# theFlower.net
KiCad netlist of a schematic drawn in EAGLE
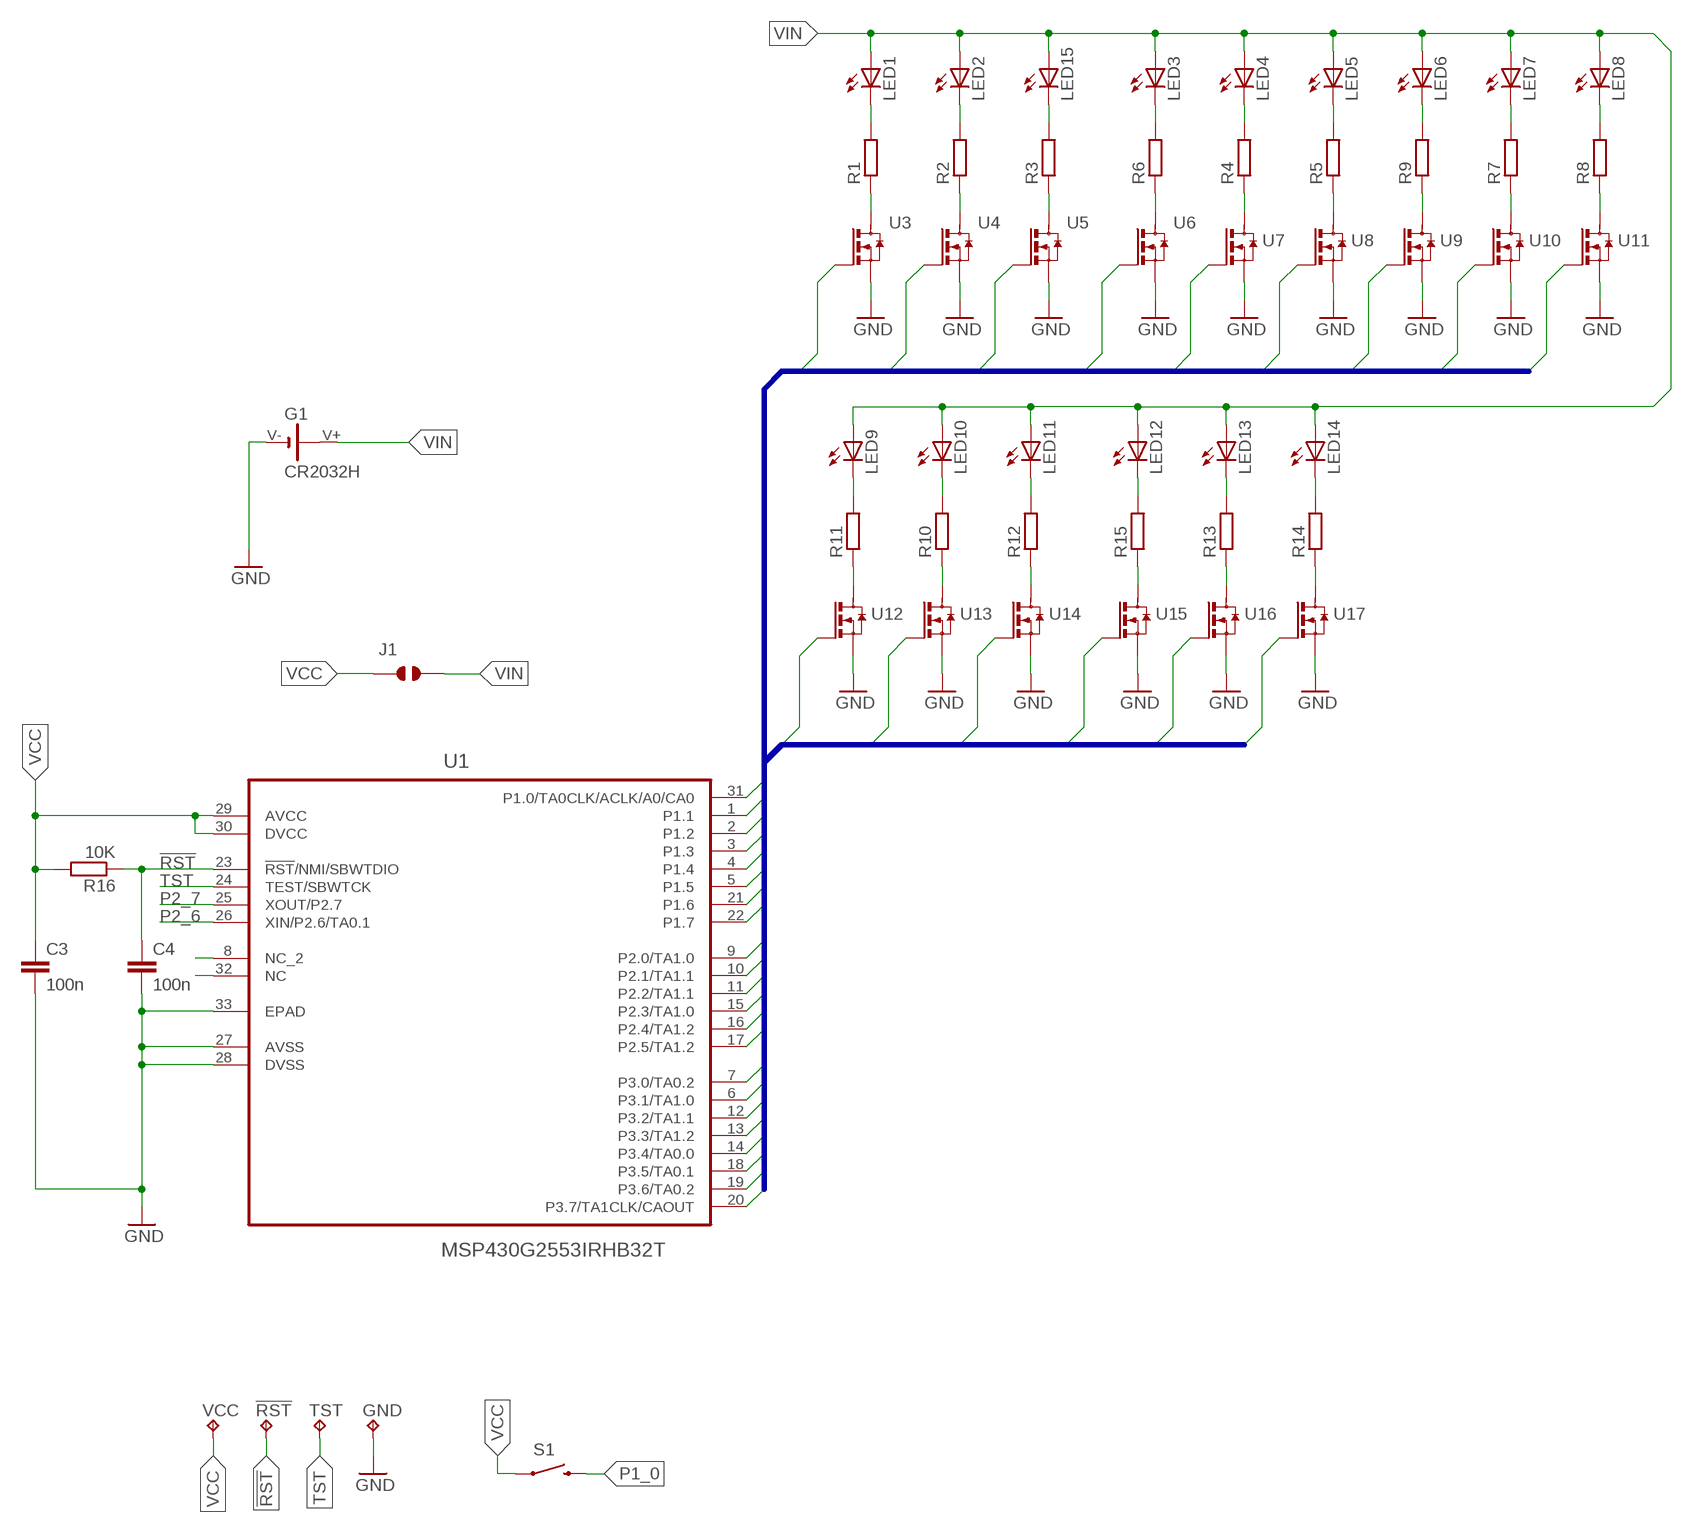
[diagram p0: schematic, sheet 1]

(export (version "E")
  (design (tool "Eeschema 10.0.6"))
  (components
    (comp (ref "!RST!")
      (value "TPAD0.8MM_RUND")
      (footprint "eagle-import:TPAD_0.8MM_RUND")
      (libsource (lib "eagle-import") (part "TPAD0.8MM_RUND"))
    )
    (comp (ref "C3")
      (value "100n")
      (footprint "eagle-import:C0603")
      (libsource (lib "eagle-import") (part "C-EUC0603"))
    )
    (comp (ref "C4")
      (value "100n")
      (footprint "eagle-import:C0603")
      (libsource (lib "eagle-import") (part "C-EUC0603"))
    )
    (comp (ref "G1")
      (value "CR2032H")
      (footprint "eagle-import:CH7410-2032LF")
      (libsource (lib "eagle-import") (part "CR2032H"))
    )
    (comp (ref "GND")
      (value "TPAD0.8MM_RUND")
      (footprint "eagle-import:TPAD_0.8MM_RUND")
      (libsource (lib "eagle-import") (part "TPAD0.8MM_RUND"))
    )
    (comp (ref "J1")
      (value "JUMPER_SOLDER_1X2")
      (footprint "eagle-import:JUMPER_SOLDER_1X2")
      (libsource (lib "eagle-import") (part "JUMPER_SOLDER_1X2"))
    )
    (comp (ref "LED1")
      (value "LEDCHIP-LED0805")
      (footprint "eagle-import:CHIP-LED0805")
      (libsource (lib "eagle-import") (part "LEDCHIP-LED0805"))
    )
    (comp (ref "LED2")
      (value "LEDCHIP-LED0805")
      (footprint "eagle-import:CHIP-LED0805")
      (libsource (lib "eagle-import") (part "LEDCHIP-LED0805"))
    )
    (comp (ref "LED3")
      (value "LEDCHIP-LED0805")
      (footprint "eagle-import:CHIP-LED0805")
      (libsource (lib "eagle-import") (part "LEDCHIP-LED0805"))
    )
    (comp (ref "LED4")
      (value "LEDCHIP-LED0805")
      (footprint "eagle-import:CHIP-LED0805")
      (libsource (lib "eagle-import") (part "LEDCHIP-LED0805"))
    )
    (comp (ref "LED5")
      (value "LEDCHIP-LED0805")
      (footprint "eagle-import:CHIP-LED0805")
      (libsource (lib "eagle-import") (part "LEDCHIP-LED0805"))
    )
    (comp (ref "LED6")
      (value "LEDCHIP-LED0805")
      (footprint "eagle-import:CHIP-LED0805")
      (libsource (lib "eagle-import") (part "LEDCHIP-LED0805"))
    )
    (comp (ref "LED7")
      (value "LEDCHIP-LED0805")
      (footprint "eagle-import:CHIP-LED0805")
      (libsource (lib "eagle-import") (part "LEDCHIP-LED0805"))
    )
    (comp (ref "LED8")
      (value "LEDCHIP-LED0805")
      (footprint "eagle-import:CHIP-LED0805")
      (libsource (lib "eagle-import") (part "LEDCHIP-LED0805"))
    )
    (comp (ref "LED9")
      (value "LEDCHIP-LED0805")
      (footprint "eagle-import:CHIP-LED0805")
      (libsource (lib "eagle-import") (part "LEDCHIP-LED0805"))
    )
    (comp (ref "LED10")
      (value "LEDCHIP-LED0805")
      (footprint "eagle-import:CHIP-LED0805")
      (libsource (lib "eagle-import") (part "LEDCHIP-LED0805"))
    )
    (comp (ref "LED11")
      (value "LEDCHIP-LED0805")
      (footprint "eagle-import:CHIP-LED0805")
      (libsource (lib "eagle-import") (part "LEDCHIP-LED0805"))
    )
    (comp (ref "LED12")
      (value "LEDCHIP-LED0805")
      (footprint "eagle-import:CHIP-LED0805")
      (libsource (lib "eagle-import") (part "LEDCHIP-LED0805"))
    )
    (comp (ref "LED13")
      (value "LEDCHIP-LED0805")
      (footprint "eagle-import:CHIP-LED0805")
      (libsource (lib "eagle-import") (part "LEDCHIP-LED0805"))
    )
    (comp (ref "LED14")
      (value "LEDCHIP-LED0805")
      (footprint "eagle-import:CHIP-LED0805")
      (libsource (lib "eagle-import") (part "LEDCHIP-LED0805"))
    )
    (comp (ref "LED15")
      (value "LEDCHIP-LED0805")
      (footprint "eagle-import:CHIP-LED0805")
      (libsource (lib "eagle-import") (part "LEDCHIP-LED0805"))
    )
    (comp (ref "R1")
      (value "R-EU_R0603")
      (footprint "eagle-import:R0603")
      (libsource (lib "eagle-import") (part "R-EU_R0603"))
    )
    (comp (ref "R2")
      (value "R-EU_R0603")
      (footprint "eagle-import:R0603")
      (libsource (lib "eagle-import") (part "R-EU_R0603"))
    )
    (comp (ref "R3")
      (value "R-EU_R0603")
      (footprint "eagle-import:R0603")
      (libsource (lib "eagle-import") (part "R-EU_R0603"))
    )
    (comp (ref "R4")
      (value "R-EU_R0603")
      (footprint "eagle-import:R0603")
      (libsource (lib "eagle-import") (part "R-EU_R0603"))
    )
    (comp (ref "R5")
      (value "R-EU_R0603")
      (footprint "eagle-import:R0603")
      (libsource (lib "eagle-import") (part "R-EU_R0603"))
    )
    (comp (ref "R6")
      (value "R-EU_R0603")
      (footprint "eagle-import:R0603")
      (libsource (lib "eagle-import") (part "R-EU_R0603"))
    )
    (comp (ref "R7")
      (value "R-EU_R0603")
      (footprint "eagle-import:R0603")
      (libsource (lib "eagle-import") (part "R-EU_R0603"))
    )
    (comp (ref "R8")
      (value "R-EU_R0603")
      (footprint "eagle-import:R0603")
      (libsource (lib "eagle-import") (part "R-EU_R0603"))
    )
    (comp (ref "R9")
      (value "R-EU_R0603")
      (footprint "eagle-import:R0603")
      (libsource (lib "eagle-import") (part "R-EU_R0603"))
    )
    (comp (ref "R10")
      (value "R-EU_R0603")
      (footprint "eagle-import:R0603")
      (libsource (lib "eagle-import") (part "R-EU_R0603"))
    )
    (comp (ref "R11")
      (value "R-EU_R0603")
      (footprint "eagle-import:R0603")
      (libsource (lib "eagle-import") (part "R-EU_R0603"))
    )
    (comp (ref "R12")
      (value "R-EU_R0603")
      (footprint "eagle-import:R0603")
      (libsource (lib "eagle-import") (part "R-EU_R0603"))
    )
    (comp (ref "R13")
      (value "R-EU_R0603")
      (footprint "eagle-import:R0603")
      (libsource (lib "eagle-import") (part "R-EU_R0603"))
    )
    (comp (ref "R14")
      (value "R-EU_R0603")
      (footprint "eagle-import:R0603")
      (libsource (lib "eagle-import") (part "R-EU_R0603"))
    )
    (comp (ref "R15")
      (value "R-EU_R0603")
      (footprint "eagle-import:R0603")
      (libsource (lib "eagle-import") (part "R-EU_R0603"))
    )
    (comp (ref "R16")
      (value "10K")
      (footprint "eagle-import:R0603")
      (libsource (lib "eagle-import") (part "R-EU_R0603"))
    )
    (comp (ref "S1")
      (value "SWITCH-MOMENTARY-2SMD")
      (footprint "eagle-import:TACTILE-SWITCH-SMD")
      (libsource (lib "eagle-import") (part "SWITCH-MOMENTARY-2SMD"))
    )
    (comp (ref "TST")
      (value "TPAD0.8MM_RUND")
      (footprint "eagle-import:TPAD_0.8MM_RUND")
      (libsource (lib "eagle-import") (part "TPAD0.8MM_RUND"))
    )
    (comp (ref "U1")
      (value "MSP430G2553IRHB32T")
      (footprint "eagle-import:QFN50P500X500X100-33N")
      (libsource (lib "eagle-import") (part "MSP430G2553IRHB32T"))
    )
    (comp (ref "U3")
      (value "BSS138BKW")
      (footprint "eagle-import:SOT65P210X110-3N")
      (libsource (lib "eagle-import") (part "BSS138BKW"))
    )
    (comp (ref "U4")
      (value "BSS138BKW")
      (footprint "eagle-import:SOT65P210X110-3N")
      (libsource (lib "eagle-import") (part "BSS138BKW"))
    )
    (comp (ref "U5")
      (value "BSS138BKW")
      (footprint "eagle-import:SOT65P210X110-3N")
      (libsource (lib "eagle-import") (part "BSS138BKW"))
    )
    (comp (ref "U6")
      (value "BSS138BKW")
      (footprint "eagle-import:SOT65P210X110-3N")
      (libsource (lib "eagle-import") (part "BSS138BKW"))
    )
    (comp (ref "U7")
      (value "BSS138BKW")
      (footprint "eagle-import:SOT65P210X110-3N")
      (libsource (lib "eagle-import") (part "BSS138BKW"))
    )
    (comp (ref "U8")
      (value "BSS138BKW")
      (footprint "eagle-import:SOT65P210X110-3N")
      (libsource (lib "eagle-import") (part "BSS138BKW"))
    )
    (comp (ref "U9")
      (value "BSS138BKW")
      (footprint "eagle-import:SOT65P210X110-3N")
      (libsource (lib "eagle-import") (part "BSS138BKW"))
    )
    (comp (ref "U10")
      (value "BSS138BKW")
      (footprint "eagle-import:SOT65P210X110-3N")
      (libsource (lib "eagle-import") (part "BSS138BKW"))
    )
    (comp (ref "U11")
      (value "BSS138BKW")
      (footprint "eagle-import:SOT65P210X110-3N")
      (libsource (lib "eagle-import") (part "BSS138BKW"))
    )
    (comp (ref "U12")
      (value "BSS138BKW")
      (footprint "eagle-import:SOT65P210X110-3N")
      (libsource (lib "eagle-import") (part "BSS138BKW"))
    )
    (comp (ref "U13")
      (value "BSS138BKW")
      (footprint "eagle-import:SOT65P210X110-3N")
      (libsource (lib "eagle-import") (part "BSS138BKW"))
    )
    (comp (ref "U14")
      (value "BSS138BKW")
      (footprint "eagle-import:SOT65P210X110-3N")
      (libsource (lib "eagle-import") (part "BSS138BKW"))
    )
    (comp (ref "U15")
      (value "BSS138BKW")
      (footprint "eagle-import:SOT65P210X110-3N")
      (libsource (lib "eagle-import") (part "BSS138BKW"))
    )
    (comp (ref "U16")
      (value "BSS138BKW")
      (footprint "eagle-import:SOT65P210X110-3N")
      (libsource (lib "eagle-import") (part "BSS138BKW"))
    )
    (comp (ref "U17")
      (value "BSS138BKW")
      (footprint "eagle-import:SOT65P210X110-3N")
      (libsource (lib "eagle-import") (part "BSS138BKW"))
    )
    (comp (ref "VCC")
      (value "TPAD0.8MM_RUND")
      (footprint "eagle-import:TPAD_0.8MM_RUND")
      (libsource (lib "eagle-import") (part "TPAD0.8MM_RUND"))
    )
  )
  (nets
    (net (code "1") (name "/P1_1") (class "Default")
      (node (ref "U1") (pin "1") (pinfunction "P1.1_1") (pintype "bidirectional"))
      (node (ref "U5") (pin "1") (pinfunction "G_1") (pintype "passive"))
    )
    (net (code "2") (name "/P1_2") (class "Default")
      (node (ref "U1") (pin "2") (pinfunction "P1.2_2") (pintype "bidirectional"))
      (node (ref "U3") (pin "1") (pinfunction "G_1") (pintype "passive"))
    )
    (net (code "3") (name "/P1_3") (class "Default")
      (node (ref "U1") (pin "3") (pinfunction "P1.3_3") (pintype "bidirectional"))
      (node (ref "U4") (pin "1") (pinfunction "G_1") (pintype "passive"))
    )
    (net (code "4") (name "/P1_4") (class "Default")
      (node (ref "U1") (pin "4") (pinfunction "P1.4_4") (pintype "bidirectional"))
      (node (ref "U6") (pin "1") (pinfunction "G_1") (pintype "passive"))
    )
    (net (code "5") (name "/P1_5") (class "Default")
      (node (ref "U1") (pin "5") (pinfunction "P1.5_5") (pintype "bidirectional"))
      (node (ref "U7") (pin "1") (pinfunction "G_1") (pintype "passive"))
    )
    (net (code "6") (name "/P1_6") (class "Default")
      (node (ref "U1") (pin "21") (pinfunction "P1.6_21") (pintype "bidirectional"))
      (node (ref "U16") (pin "1") (pinfunction "G_1") (pintype "passive"))
    )
    (net (code "7") (name "/P1_7") (class "Default")
      (node (ref "U1") (pin "22") (pinfunction "P1.7_22") (pintype "bidirectional"))
      (node (ref "U17") (pin "1") (pinfunction "G_1") (pintype "passive"))
    )
    (net (code "8") (name "/P2_0") (class "Default")
      (node (ref "U1") (pin "9") (pinfunction "P2.0/TA1.0_9") (pintype "bidirectional"))
      (node (ref "U10") (pin "1") (pinfunction "G_1") (pintype "passive"))
    )
    (net (code "9") (name "/P2_1") (class "Default")
      (node (ref "U1") (pin "10") (pinfunction "P2.1/TA1.1_10") (pintype "bidirectional"))
      (node (ref "U11") (pin "1") (pinfunction "G_1") (pintype "passive"))
    )
    (net (code "10") (name "/P2_2") (class "Default")
      (node (ref "U1") (pin "11") (pinfunction "P2.2/TA1.1_11") (pintype "bidirectional"))
      (node (ref "U12") (pin "1") (pinfunction "G_1") (pintype "passive"))
    )
    (net (code "11") (name "/P2_6") (class "Default")
      (node (ref "U1") (pin "26") (pinfunction "XIN/P2.6/TA0.1_26") (pintype "bidirectional"))
    )
    (net (code "12") (name "/P2_7") (class "Default")
      (node (ref "U1") (pin "25") (pinfunction "XOUT/P2.7_25") (pintype "bidirectional"))
    )
    (net (code "13") (name "/P3_0") (class "Default")
      (node (ref "U1") (pin "7") (pinfunction "P3.0/TA0.2_7") (pintype "bidirectional"))
      (node (ref "U9") (pin "1") (pinfunction "G_1") (pintype "passive"))
    )
    (net (code "14") (name "/P3_1") (class "Default")
      (node (ref "U1") (pin "6") (pinfunction "P3.1/TA1.0_6") (pintype "bidirectional"))
      (node (ref "U8") (pin "1") (pinfunction "G_1") (pintype "passive"))
    )
    (net (code "15") (name "/P3_2") (class "Default")
      (node (ref "U1") (pin "12") (pinfunction "P3.2/TA1.1_12") (pintype "bidirectional"))
      (node (ref "U13") (pin "1") (pinfunction "G_1") (pintype "passive"))
    )
    (net (code "16") (name "/P3_3") (class "Default")
      (node (ref "U1") (pin "13") (pinfunction "P3.3/TA1.2_13") (pintype "bidirectional"))
      (node (ref "U14") (pin "1") (pinfunction "G_1") (pintype "passive"))
    )
    (net (code "17") (name "/P3_7") (class "Default")
      (node (ref "U1") (pin "20") (pinfunction "P3.7/TA1CLK/CAOUT_20") (pintype "bidirectional"))
      (node (ref "U15") (pin "1") (pinfunction "G_1") (pintype "passive"))
    )
    (net (code "18") (name "/~{RST}") (class "Default")
      (node (ref "!RST!") (pin "1") (pinfunction "TP_1") (pintype "input"))
      (node (ref "C4") (pin "1") (pinfunction "1_1") (pintype "passive"))
      (node (ref "R16") (pin "1") (pinfunction "1_1") (pintype "passive"))
      (node (ref "U1") (pin "23") (pinfunction "~{RST}/NMI/SBWTDIO_23") (pintype "bidirectional"))
    )
    (net (code "19") (name "GND") (class "Default")
      (node (ref "C3") (pin "2") (pinfunction "2_2") (pintype "passive"))
      (node (ref "C4") (pin "2") (pinfunction "2_2") (pintype "passive"))
      (node (ref "G1") (pin "V-") (pinfunction "V-_V-") (pintype "passive"))
      (node (ref "GND") (pin "1") (pinfunction "TP_1") (pintype "input"))
      (node (ref "U1") (pin "27") (pinfunction "AVSS_27") (pintype "passive"))
      (node (ref "U1") (pin "28") (pinfunction "DVSS_28") (pintype "passive"))
      (node (ref "U1") (pin "33") (pinfunction "EPAD_33") (pintype "passive"))
      (node (ref "U10") (pin "2") (pinfunction "S_2") (pintype "passive"))
      (node (ref "U11") (pin "2") (pinfunction "S_2") (pintype "passive"))
      (node (ref "U12") (pin "2") (pinfunction "S_2") (pintype "passive"))
      (node (ref "U13") (pin "2") (pinfunction "S_2") (pintype "passive"))
      (node (ref "U14") (pin "2") (pinfunction "S_2") (pintype "passive"))
      (node (ref "U15") (pin "2") (pinfunction "S_2") (pintype "passive"))
      (node (ref "U16") (pin "2") (pinfunction "S_2") (pintype "passive"))
      (node (ref "U17") (pin "2") (pinfunction "S_2") (pintype "passive"))
      (node (ref "U3") (pin "2") (pinfunction "S_2") (pintype "passive"))
      (node (ref "U4") (pin "2") (pinfunction "S_2") (pintype "passive"))
      (node (ref "U5") (pin "2") (pinfunction "S_2") (pintype "passive"))
      (node (ref "U6") (pin "2") (pinfunction "S_2") (pintype "passive"))
      (node (ref "U7") (pin "2") (pinfunction "S_2") (pintype "passive"))
      (node (ref "U8") (pin "2") (pinfunction "S_2") (pintype "passive"))
      (node (ref "U9") (pin "2") (pinfunction "S_2") (pintype "passive"))
    )
    (net (code "20") (name "Net-(LED1-PadC)") (class "Default")
      (node (ref "LED1") (pin "C") (pinfunction "C_C") (pintype "passive"))
      (node (ref "R1") (pin "2") (pinfunction "2_2") (pintype "passive"))
    )
    (net (code "21") (name "Net-(LED2-PadC)") (class "Default")
      (node (ref "LED2") (pin "C") (pinfunction "C_C") (pintype "passive"))
      (node (ref "R2") (pin "2") (pinfunction "2_2") (pintype "passive"))
    )
    (net (code "22") (name "Net-(LED3-PadC)") (class "Default")
      (node (ref "LED3") (pin "C") (pinfunction "C_C") (pintype "passive"))
      (node (ref "R6") (pin "2") (pinfunction "2_2") (pintype "passive"))
    )
    (net (code "23") (name "Net-(LED4-PadC)") (class "Default")
      (node (ref "LED4") (pin "C") (pinfunction "C_C") (pintype "passive"))
      (node (ref "R4") (pin "2") (pinfunction "2_2") (pintype "passive"))
    )
    (net (code "24") (name "Net-(LED5-PadC)") (class "Default")
      (node (ref "LED5") (pin "C") (pinfunction "C_C") (pintype "passive"))
      (node (ref "R5") (pin "2") (pinfunction "2_2") (pintype "passive"))
    )
    (net (code "25") (name "Net-(LED6-PadC)") (class "Default")
      (node (ref "LED6") (pin "C") (pinfunction "C_C") (pintype "passive"))
      (node (ref "R9") (pin "2") (pinfunction "2_2") (pintype "passive"))
    )
    (net (code "26") (name "Net-(LED7-PadC)") (class "Default")
      (node (ref "LED7") (pin "C") (pinfunction "C_C") (pintype "passive"))
      (node (ref "R7") (pin "2") (pinfunction "2_2") (pintype "passive"))
    )
    (net (code "27") (name "Net-(LED8-PadC)") (class "Default")
      (node (ref "LED8") (pin "C") (pinfunction "C_C") (pintype "passive"))
      (node (ref "R8") (pin "2") (pinfunction "2_2") (pintype "passive"))
    )
    (net (code "28") (name "Net-(LED9-PadC)") (class "Default")
      (node (ref "LED9") (pin "C") (pinfunction "C_C") (pintype "passive"))
      (node (ref "R11") (pin "2") (pinfunction "2_2") (pintype "passive"))
    )
    (net (code "29") (name "Net-(LED10-PadC)") (class "Default")
      (node (ref "LED10") (pin "C") (pinfunction "C_C") (pintype "passive"))
      (node (ref "R10") (pin "2") (pinfunction "2_2") (pintype "passive"))
    )
    (net (code "30") (name "Net-(LED11-PadC)") (class "Default")
      (node (ref "LED11") (pin "C") (pinfunction "C_C") (pintype "passive"))
      (node (ref "R12") (pin "2") (pinfunction "2_2") (pintype "passive"))
    )
    (net (code "31") (name "Net-(LED12-PadC)") (class "Default")
      (node (ref "LED12") (pin "C") (pinfunction "C_C") (pintype "passive"))
      (node (ref "R15") (pin "2") (pinfunction "2_2") (pintype "passive"))
    )
    (net (code "32") (name "Net-(LED13-PadC)") (class "Default")
      (node (ref "LED13") (pin "C") (pinfunction "C_C") (pintype "passive"))
      (node (ref "R13") (pin "2") (pinfunction "2_2") (pintype "passive"))
    )
    (net (code "33") (name "Net-(LED14-PadC)") (class "Default")
      (node (ref "LED14") (pin "C") (pinfunction "C_C") (pintype "passive"))
      (node (ref "R14") (pin "2") (pinfunction "2_2") (pintype "passive"))
    )
    (net (code "34") (name "Net-(LED15-PadC)") (class "Default")
      (node (ref "LED15") (pin "C") (pinfunction "C_C") (pintype "passive"))
      (node (ref "R3") (pin "2") (pinfunction "2_2") (pintype "passive"))
    )
    (net (code "35") (name "Net-(U3-D)") (class "Default")
      (node (ref "R1") (pin "1") (pinfunction "1_1") (pintype "passive"))
      (node (ref "U3") (pin "3") (pinfunction "D_3") (pintype "passive"))
    )
    (net (code "36") (name "Net-(U4-D)") (class "Default")
      (node (ref "R2") (pin "1") (pinfunction "1_1") (pintype "passive"))
      (node (ref "U4") (pin "3") (pinfunction "D_3") (pintype "passive"))
    )
    (net (code "37") (name "Net-(U5-D)") (class "Default")
      (node (ref "R3") (pin "1") (pinfunction "1_1") (pintype "passive"))
      (node (ref "U5") (pin "3") (pinfunction "D_3") (pintype "passive"))
    )
    (net (code "38") (name "Net-(U6-D)") (class "Default")
      (node (ref "R6") (pin "1") (pinfunction "1_1") (pintype "passive"))
      (node (ref "U6") (pin "3") (pinfunction "D_3") (pintype "passive"))
    )
    (net (code "39") (name "Net-(U7-D)") (class "Default")
      (node (ref "R4") (pin "1") (pinfunction "1_1") (pintype "passive"))
      (node (ref "U7") (pin "3") (pinfunction "D_3") (pintype "passive"))
    )
    (net (code "40") (name "Net-(U8-D)") (class "Default")
      (node (ref "R5") (pin "1") (pinfunction "1_1") (pintype "passive"))
      (node (ref "U8") (pin "3") (pinfunction "D_3") (pintype "passive"))
    )
    (net (code "41") (name "Net-(U9-D)") (class "Default")
      (node (ref "R9") (pin "1") (pinfunction "1_1") (pintype "passive"))
      (node (ref "U9") (pin "3") (pinfunction "D_3") (pintype "passive"))
    )
    (net (code "42") (name "Net-(U10-D)") (class "Default")
      (node (ref "R7") (pin "1") (pinfunction "1_1") (pintype "passive"))
      (node (ref "U10") (pin "3") (pinfunction "D_3") (pintype "passive"))
    )
    (net (code "43") (name "Net-(U11-D)") (class "Default")
      (node (ref "R8") (pin "1") (pinfunction "1_1") (pintype "passive"))
      (node (ref "U11") (pin "3") (pinfunction "D_3") (pintype "passive"))
    )
    (net (code "44") (name "Net-(U12-D)") (class "Default")
      (node (ref "R11") (pin "1") (pinfunction "1_1") (pintype "passive"))
      (node (ref "U12") (pin "3") (pinfunction "D_3") (pintype "passive"))
    )
    (net (code "45") (name "Net-(U13-D)") (class "Default")
      (node (ref "R10") (pin "1") (pinfunction "1_1") (pintype "passive"))
      (node (ref "U13") (pin "3") (pinfunction "D_3") (pintype "passive"))
    )
    (net (code "46") (name "Net-(U14-D)") (class "Default")
      (node (ref "R12") (pin "1") (pinfunction "1_1") (pintype "passive"))
      (node (ref "U14") (pin "3") (pinfunction "D_3") (pintype "passive"))
    )
    (net (code "47") (name "Net-(U15-D)") (class "Default")
      (node (ref "R15") (pin "1") (pinfunction "1_1") (pintype "passive"))
      (node (ref "U15") (pin "3") (pinfunction "D_3") (pintype "passive"))
    )
    (net (code "48") (name "Net-(U16-D)") (class "Default")
      (node (ref "R13") (pin "1") (pinfunction "1_1") (pintype "passive"))
      (node (ref "U16") (pin "3") (pinfunction "D_3") (pintype "passive"))
    )
    (net (code "49") (name "Net-(U17-D)") (class "Default")
      (node (ref "R14") (pin "1") (pinfunction "1_1") (pintype "passive"))
      (node (ref "U17") (pin "3") (pinfunction "D_3") (pintype "passive"))
    )
    (net (code "50") (name "P1_0") (class "Default")
      (node (ref "S1") (pin "3") (pinfunction "2_3") (pintype "passive"))
      (node (ref "U1") (pin "31") (pinfunction "P1.0/TA0CLK/ACLK/A0/CA0_31") (pintype "bidirectional"))
    )
    (net (code "51") (name "TST") (class "Default")
      (node (ref "TST") (pin "1") (pinfunction "TP_1") (pintype "input"))
      (node (ref "U1") (pin "24") (pinfunction "TEST/SBWTCK_24") (pintype "bidirectional"))
    )
    (net (code "52") (name "VCC") (class "Default")
      (node (ref "C3") (pin "1") (pinfunction "1_1") (pintype "passive"))
      (node (ref "J1") (pin "1") (pinfunction "1_1") (pintype "passive"))
      (node (ref "R16") (pin "2") (pinfunction "2_2") (pintype "passive"))
      (node (ref "S1") (pin "1") (pinfunction "1_1") (pintype "passive"))
      (node (ref "U1") (pin "29") (pinfunction "AVCC_29") (pintype "power_in"))
      (node (ref "U1") (pin "30") (pinfunction "DVCC_30") (pintype "power_in"))
      (node (ref "VCC") (pin "1") (pinfunction "TP_1") (pintype "input"))
    )
    (net (code "53") (name "VIN") (class "Default")
      (node (ref "G1") (pin "V+") (pinfunction "V+_V+") (pintype "passive"))
      (node (ref "J1") (pin "2") (pinfunction "2_2") (pintype "passive"))
      (node (ref "LED1") (pin "A") (pinfunction "A_A") (pintype "passive"))
      (node (ref "LED10") (pin "A") (pinfunction "A_A") (pintype "passive"))
      (node (ref "LED11") (pin "A") (pinfunction "A_A") (pintype "passive"))
      (node (ref "LED12") (pin "A") (pinfunction "A_A") (pintype "passive"))
      (node (ref "LED13") (pin "A") (pinfunction "A_A") (pintype "passive"))
      (node (ref "LED14") (pin "A") (pinfunction "A_A") (pintype "passive"))
      (node (ref "LED15") (pin "A") (pinfunction "A_A") (pintype "passive"))
      (node (ref "LED2") (pin "A") (pinfunction "A_A") (pintype "passive"))
      (node (ref "LED3") (pin "A") (pinfunction "A_A") (pintype "passive"))
      (node (ref "LED4") (pin "A") (pinfunction "A_A") (pintype "passive"))
      (node (ref "LED5") (pin "A") (pinfunction "A_A") (pintype "passive"))
      (node (ref "LED6") (pin "A") (pinfunction "A_A") (pintype "passive"))
      (node (ref "LED7") (pin "A") (pinfunction "A_A") (pintype "passive"))
      (node (ref "LED8") (pin "A") (pinfunction "A_A") (pintype "passive"))
      (node (ref "LED9") (pin "A") (pinfunction "A_A") (pintype "passive"))
    )
    (net (code "54") (name "unconnected-(U1-NC-Pad32)") (class "Default")
      (node (ref "U1") (pin "32") (pinfunction "NC_32") (pintype "no_connect"))
    )
    (net (code "55") (name "unconnected-(U1-NC_2-Pad8)") (class "Default")
      (node (ref "U1") (pin "8") (pinfunction "NC_2_8") (pintype "no_connect"))
    )
    (net (code "56") (name "unconnected-(U1-P2.3{slash}TA1.0-Pad15)") (class "Default")
      (node (ref "U1") (pin "15") (pinfunction "P2.3/TA1.0_15") (pintype "bidirectional"))
    )
    (net (code "57") (name "unconnected-(U1-P2.4{slash}TA1.2-Pad16)") (class "Default")
      (node (ref "U1") (pin "16") (pinfunction "P2.4/TA1.2_16") (pintype "bidirectional"))
    )
    (net (code "58") (name "unconnected-(U1-P2.5{slash}TA1.2-Pad17)") (class "Default")
      (node (ref "U1") (pin "17") (pinfunction "P2.5/TA1.2_17") (pintype "bidirectional"))
    )
    (net (code "59") (name "unconnected-(U1-P3.4{slash}TA0.0-Pad14)") (class "Default")
      (node (ref "U1") (pin "14") (pinfunction "P3.4/TA0.0_14") (pintype "bidirectional"))
    )
    (net (code "60") (name "unconnected-(U1-P3.5{slash}TA0.1-Pad18)") (class "Default")
      (node (ref "U1") (pin "18") (pinfunction "P3.5/TA0.1_18") (pintype "bidirectional"))
    )
    (net (code "61") (name "unconnected-(U1-P3.6{slash}TA0.2-Pad19)") (class "Default")
      (node (ref "U1") (pin "19") (pinfunction "P3.6/TA0.2_19") (pintype "bidirectional"))
    )
  )
)
